# SUSTAINA-StrainGauge-Sensing-Board.net
KiCad netlist of a schematic drawn in EAGLE
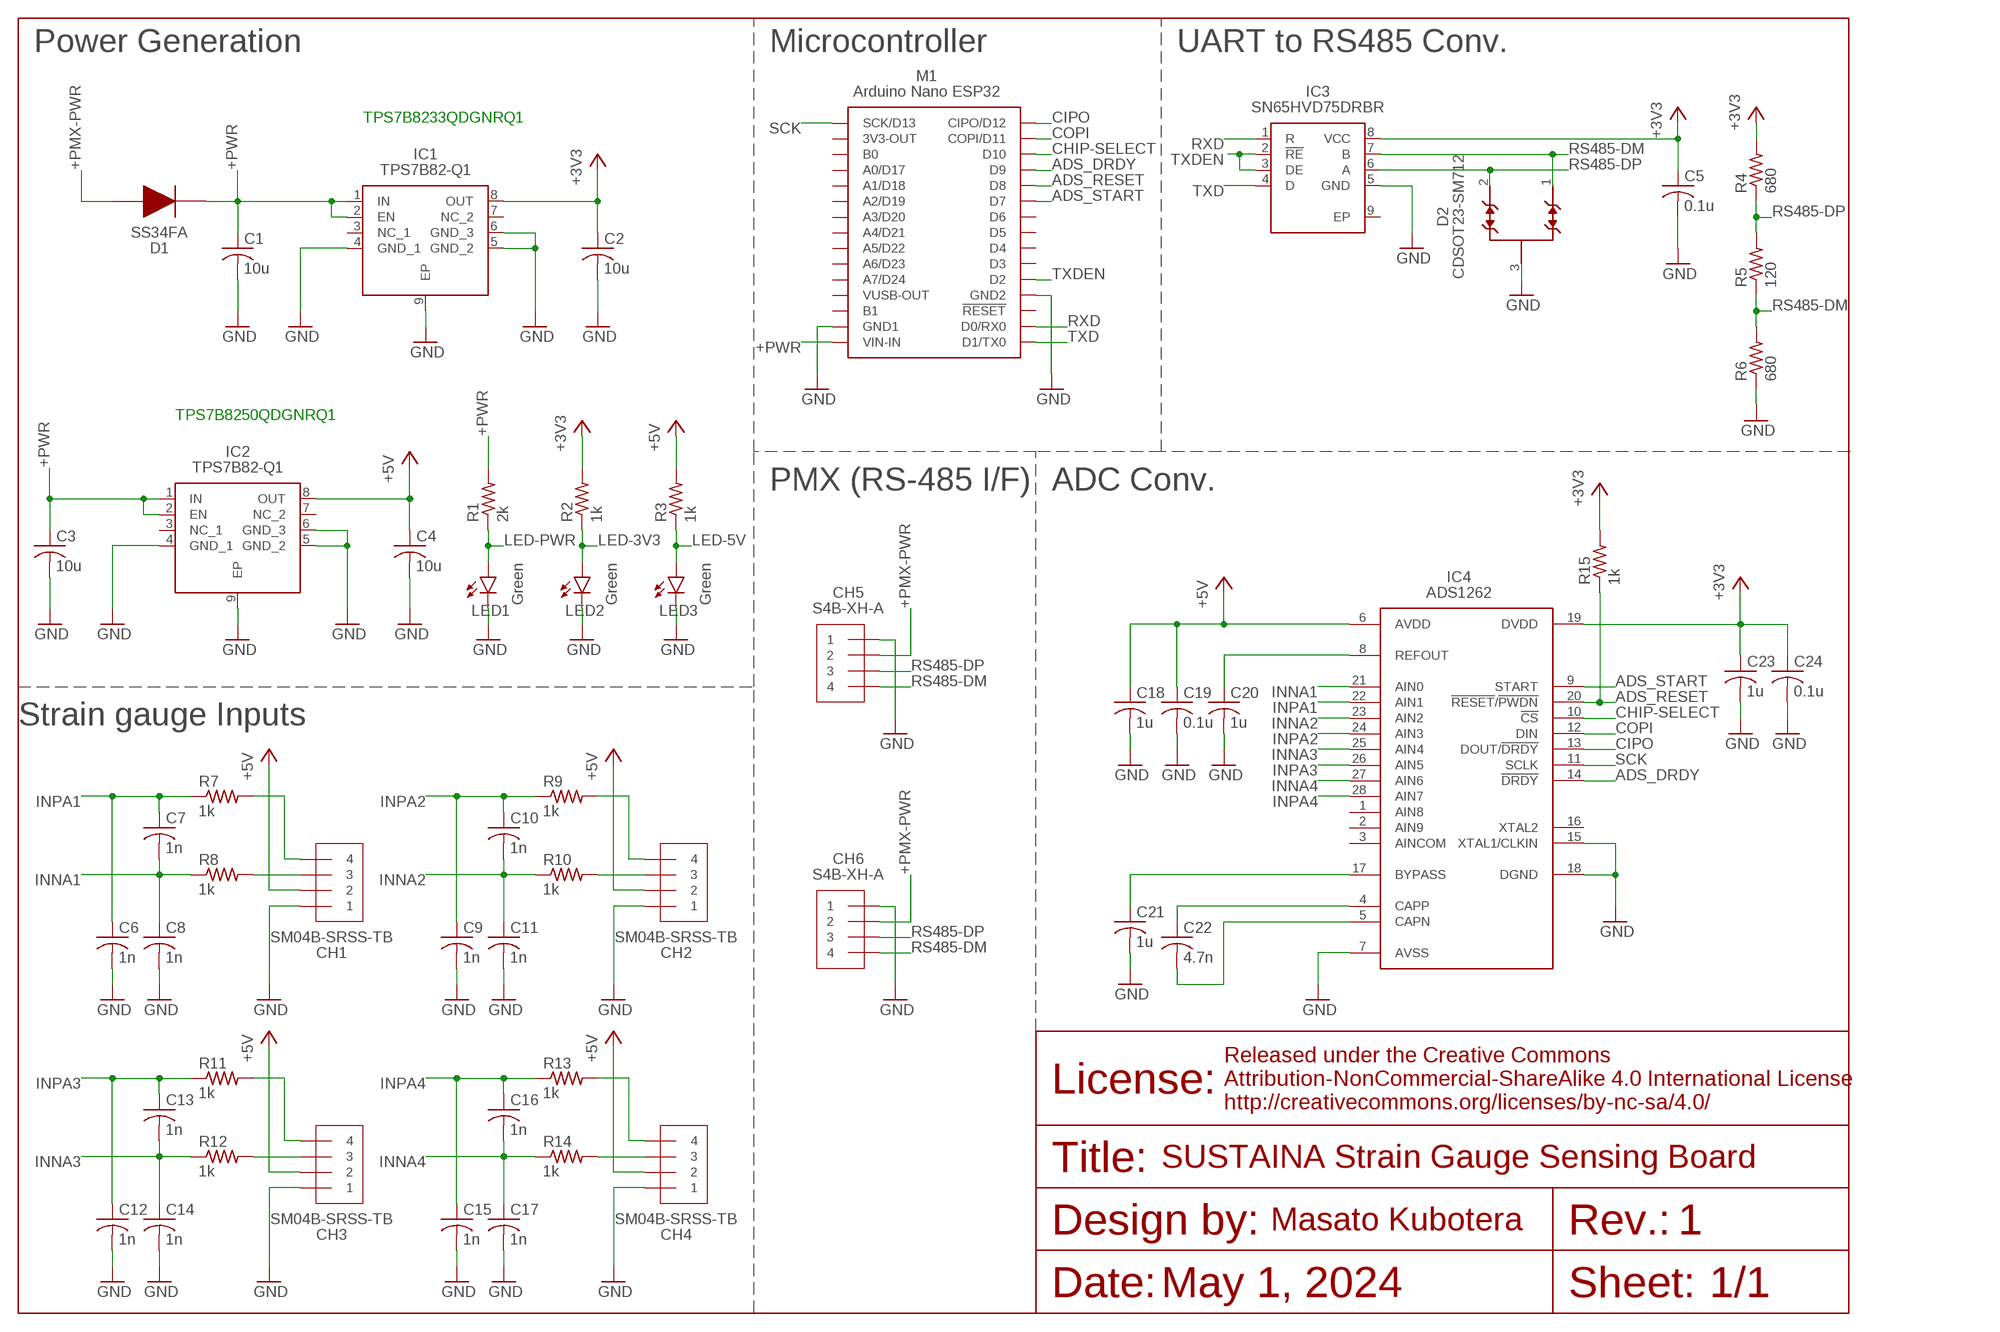
[diagram p0: schematic, sheet 1]

(export (version "E")
  (design (tool "Eeschema 10.0.6"))
  (components
    (comp (ref "C1")
      (value "10u")
      (footprint "eagle-import:C0603")
      (libsource (lib "eagle-import") (part "C-USC0603"))
    )
    (comp (ref "C2")
      (value "10u")
      (footprint "eagle-import:C0603")
      (libsource (lib "eagle-import") (part "C-USC0603"))
    )
    (comp (ref "C3")
      (value "10u")
      (footprint "eagle-import:C0603")
      (libsource (lib "eagle-import") (part "C-USC0603"))
    )
    (comp (ref "C4")
      (value "10u")
      (footprint "eagle-import:C0603")
      (libsource (lib "eagle-import") (part "C-USC0603"))
    )
    (comp (ref "C5")
      (value "0.1u")
      (footprint "eagle-import:C0603")
      (libsource (lib "eagle-import") (part "C-USC0603"))
    )
    (comp (ref "C6")
      (value "1n")
      (footprint "eagle-import:C0603")
      (libsource (lib "eagle-import") (part "C-USC0603"))
    )
    (comp (ref "C7")
      (value "1n")
      (footprint "eagle-import:C0603")
      (libsource (lib "eagle-import") (part "C-USC0603"))
    )
    (comp (ref "C8")
      (value "1n")
      (footprint "eagle-import:C0603")
      (libsource (lib "eagle-import") (part "C-USC0603"))
    )
    (comp (ref "C9")
      (value "1n")
      (footprint "eagle-import:C0603")
      (libsource (lib "eagle-import") (part "C-USC0603"))
    )
    (comp (ref "C10")
      (value "1n")
      (footprint "eagle-import:C0603")
      (libsource (lib "eagle-import") (part "C-USC0603"))
    )
    (comp (ref "C11")
      (value "1n")
      (footprint "eagle-import:C0603")
      (libsource (lib "eagle-import") (part "C-USC0603"))
    )
    (comp (ref "C12")
      (value "1n")
      (footprint "eagle-import:C0603")
      (libsource (lib "eagle-import") (part "C-USC0603"))
    )
    (comp (ref "C13")
      (value "1n")
      (footprint "eagle-import:C0603")
      (libsource (lib "eagle-import") (part "C-USC0603"))
    )
    (comp (ref "C14")
      (value "1n")
      (footprint "eagle-import:C0603")
      (libsource (lib "eagle-import") (part "C-USC0603"))
    )
    (comp (ref "C15")
      (value "1n")
      (footprint "eagle-import:C0603")
      (libsource (lib "eagle-import") (part "C-USC0603"))
    )
    (comp (ref "C16")
      (value "1n")
      (footprint "eagle-import:C0603")
      (libsource (lib "eagle-import") (part "C-USC0603"))
    )
    (comp (ref "C17")
      (value "1n")
      (footprint "eagle-import:C0603")
      (libsource (lib "eagle-import") (part "C-USC0603"))
    )
    (comp (ref "C18")
      (value "1u")
      (footprint "eagle-import:C0603")
      (libsource (lib "eagle-import") (part "C-USC0603"))
    )
    (comp (ref "C19")
      (value "0.1u")
      (footprint "eagle-import:C0603")
      (libsource (lib "eagle-import") (part "C-USC0603"))
    )
    (comp (ref "C20")
      (value "1u")
      (footprint "eagle-import:C0603")
      (libsource (lib "eagle-import") (part "C-USC0603"))
    )
    (comp (ref "C21")
      (value "1u")
      (footprint "eagle-import:C0603")
      (libsource (lib "eagle-import") (part "C-USC0603"))
    )
    (comp (ref "C22")
      (value "4.7n")
      (footprint "eagle-import:C0603")
      (libsource (lib "eagle-import") (part "C-USC0603"))
    )
    (comp (ref "C23")
      (value "1u")
      (footprint "eagle-import:C0603")
      (libsource (lib "eagle-import") (part "C-USC0603"))
    )
    (comp (ref "C24")
      (value "0.1u")
      (footprint "eagle-import:C0603")
      (libsource (lib "eagle-import") (part "C-USC0603"))
    )
    (comp (ref "CH1")
      (value "SM04B-SRSS-TB")
      (footprint "eagle-import:SM04B-SRSS-TB")
      (libsource (lib "eagle-import") (part "SM04B-SRSS-TB"))
    )
    (comp (ref "CH2")
      (value "SM04B-SRSS-TB")
      (footprint "eagle-import:SM04B-SRSS-TB")
      (libsource (lib "eagle-import") (part "SM04B-SRSS-TB"))
    )
    (comp (ref "CH3")
      (value "SM04B-SRSS-TB")
      (footprint "eagle-import:SM04B-SRSS-TB")
      (libsource (lib "eagle-import") (part "SM04B-SRSS-TB"))
    )
    (comp (ref "CH4")
      (value "SM04B-SRSS-TB")
      (footprint "eagle-import:SM04B-SRSS-TB")
      (libsource (lib "eagle-import") (part "SM04B-SRSS-TB"))
    )
    (comp (ref "CH5")
      (value "S4B-XH-A")
      (footprint "eagle-import:S4B-XH-A")
      (libsource (lib "eagle-import") (part "S4B-XH-A"))
    )
    (comp (ref "CH6")
      (value "S4B-XH-A")
      (footprint "eagle-import:S4B-XH-A")
      (libsource (lib "eagle-import") (part "S4B-XH-A"))
    )
    (comp (ref "D1")
      (value "SS34FA")
      (footprint "eagle-import:SS34FA")
      (libsource (lib "eagle-import") (part "SS34FA"))
    )
    (comp (ref "D2")
      (value "CDSOT23-SM712")
      (footprint "eagle-import:SOT-23-3")
      (libsource (lib "eagle-import") (part "CDSOT23-SM712"))
    )
    (comp (ref "IC1")
      (value "TPS7B82-Q1")
      (footprint "eagle-import:SOP65P490X110-9N")
      (libsource (lib "eagle-import") (part "TPS7B82-Q1"))
    )
    (comp (ref "IC2")
      (value "TPS7B82-Q1")
      (footprint "eagle-import:SOP65P490X110-9N")
      (libsource (lib "eagle-import") (part "TPS7B82-Q1"))
    )
    (comp (ref "IC3")
      (value "SN65HVD75DRBR")
      (footprint "eagle-import:SON65P300X300X100-9N")
      (libsource (lib "eagle-import") (part "SN65HVD75DRBR"))
    )
    (comp (ref "IC4")
      (value "ADS1262")
      (footprint "eagle-import:SOP65P640X120-28N")
      (libsource (lib "eagle-import") (part "ADS1262"))
    )
    (comp (ref "LED1")
      (value "Green")
      (footprint "eagle-import:SML0603")
      (libsource (lib "eagle-import") (part "LEDSML0603"))
    )
    (comp (ref "LED2")
      (value "Green")
      (footprint "eagle-import:SML0603")
      (libsource (lib "eagle-import") (part "LEDSML0603"))
    )
    (comp (ref "LED3")
      (value "Green")
      (footprint "eagle-import:SML0603")
      (libsource (lib "eagle-import") (part "LEDSML0603"))
    )
    (comp (ref "M1")
      (value "NANO-ESP32SMD")
      (footprint "eagle-import:NANO-ESP32-SMD")
      (libsource (lib "eagle-import") (part "NANO-ESP32SMD"))
    )
    (comp (ref "R1")
      (value "2k")
      (footprint "eagle-import:R0603")
      (libsource (lib "eagle-import") (part "R-US_R0603"))
    )
    (comp (ref "R2")
      (value "1k")
      (footprint "eagle-import:R0603")
      (libsource (lib "eagle-import") (part "R-US_R0603"))
    )
    (comp (ref "R3")
      (value "1k")
      (footprint "eagle-import:R0603")
      (libsource (lib "eagle-import") (part "R-US_R0603"))
    )
    (comp (ref "R4")
      (value "680")
      (footprint "eagle-import:R0603")
      (libsource (lib "eagle-import") (part "R-US_R0603"))
    )
    (comp (ref "R5")
      (value "120")
      (footprint "eagle-import:R0603")
      (libsource (lib "eagle-import") (part "R-US_R0603"))
    )
    (comp (ref "R6")
      (value "680")
      (footprint "eagle-import:R0603")
      (libsource (lib "eagle-import") (part "R-US_R0603"))
    )
    (comp (ref "R7")
      (value "1k")
      (footprint "eagle-import:R0603")
      (libsource (lib "eagle-import") (part "R-US_R0603"))
    )
    (comp (ref "R8")
      (value "1k")
      (footprint "eagle-import:R0603")
      (libsource (lib "eagle-import") (part "R-US_R0603"))
    )
    (comp (ref "R9")
      (value "1k")
      (footprint "eagle-import:R0603")
      (libsource (lib "eagle-import") (part "R-US_R0603"))
    )
    (comp (ref "R10")
      (value "1k")
      (footprint "eagle-import:R0603")
      (libsource (lib "eagle-import") (part "R-US_R0603"))
    )
    (comp (ref "R11")
      (value "1k")
      (footprint "eagle-import:R0603")
      (libsource (lib "eagle-import") (part "R-US_R0603"))
    )
    (comp (ref "R12")
      (value "1k")
      (footprint "eagle-import:R0603")
      (libsource (lib "eagle-import") (part "R-US_R0603"))
    )
    (comp (ref "R13")
      (value "1k")
      (footprint "eagle-import:R0603")
      (libsource (lib "eagle-import") (part "R-US_R0603"))
    )
    (comp (ref "R14")
      (value "1k")
      (footprint "eagle-import:R0603")
      (libsource (lib "eagle-import") (part "R-US_R0603"))
    )
    (comp (ref "R15")
      (value "1k")
      (footprint "eagle-import:R0603")
      (libsource (lib "eagle-import") (part "R-US_R0603"))
    )
  )
  (nets
    (net (code "1") (name "+3V3") (class "Default")
      (node (ref "C2") (pin "1") (pinfunction "1_1") (pintype "passive"))
      (node (ref "C23") (pin "1") (pinfunction "1_1") (pintype "passive"))
      (node (ref "C24") (pin "1") (pinfunction "1_1") (pintype "passive"))
      (node (ref "C5") (pin "1") (pinfunction "1_1") (pintype "passive"))
      (node (ref "IC1") (pin "8") (pinfunction "OUT_8") (pintype "bidirectional"))
      (node (ref "IC3") (pin "8") (pinfunction "VCC_8") (pintype "bidirectional"))
      (node (ref "IC4") (pin "19") (pinfunction "DVDD_19") (pintype "bidirectional"))
      (node (ref "R15") (pin "2") (pinfunction "2_2") (pintype "passive"))
      (node (ref "R2") (pin "2") (pinfunction "2_2") (pintype "passive"))
      (node (ref "R4") (pin "2") (pinfunction "2_2") (pintype "passive"))
    )
    (net (code "2") (name "+5V") (class "Default")
      (node (ref "C18") (pin "1") (pinfunction "1_1") (pintype "passive"))
      (node (ref "C19") (pin "1") (pinfunction "1_1") (pintype "passive"))
      (node (ref "C4") (pin "1") (pinfunction "1_1") (pintype "passive"))
      (node (ref "CH1") (pin "2") (pinfunction "2_2") (pintype "bidirectional"))
      (node (ref "CH2") (pin "2") (pinfunction "2_2") (pintype "bidirectional"))
      (node (ref "CH3") (pin "2") (pinfunction "2_2") (pintype "bidirectional"))
      (node (ref "CH4") (pin "2") (pinfunction "2_2") (pintype "bidirectional"))
      (node (ref "IC2") (pin "8") (pinfunction "OUT_8") (pintype "bidirectional"))
      (node (ref "IC4") (pin "6") (pinfunction "AVDD_6") (pintype "bidirectional"))
      (node (ref "R3") (pin "2") (pinfunction "2_2") (pintype "passive"))
    )
    (net (code "3") (name "/+PMX-PWR") (class "Default")
      (node (ref "CH5") (pin "2") (pinfunction "2_2") (pintype "bidirectional"))
      (node (ref "CH6") (pin "2") (pinfunction "2_2") (pintype "bidirectional"))
      (node (ref "D1") (pin "2") (pinfunction "2_2") (pintype "bidirectional"))
    )
    (net (code "4") (name "/+PWR") (class "Default")
      (node (ref "C1") (pin "1") (pinfunction "1_1") (pintype "passive"))
      (node (ref "C3") (pin "1") (pinfunction "1_1") (pintype "passive"))
      (node (ref "D1") (pin "1") (pinfunction "1_1") (pintype "bidirectional"))
      (node (ref "IC1") (pin "1") (pinfunction "IN_1") (pintype "bidirectional"))
      (node (ref "IC1") (pin "2") (pinfunction "EN_2") (pintype "bidirectional"))
      (node (ref "IC2") (pin "1") (pinfunction "IN_1") (pintype "bidirectional"))
      (node (ref "IC2") (pin "2") (pinfunction "EN_2") (pintype "bidirectional"))
      (node (ref "M1") (pin "VIN-IN") (pinfunction "VIN-IN_VIN-IN") (pintype "bidirectional"))
      (node (ref "R1") (pin "2") (pinfunction "2_2") (pintype "passive"))
    )
    (net (code "5") (name "/ADS_DRDY") (class "Default")
      (node (ref "IC4") (pin "14") (pinfunction "~{DRDY}_14") (pintype "bidirectional"))
      (node (ref "M1") (pin "D9") (pinfunction "D9_D9") (pintype "bidirectional"))
    )
    (net (code "6") (name "/ADS_RESET") (class "Default")
      (node (ref "IC4") (pin "20") (pinfunction "~{RESET}/~{PWDN}_20") (pintype "bidirectional"))
      (node (ref "M1") (pin "D8") (pinfunction "D8_D8") (pintype "bidirectional"))
      (node (ref "R15") (pin "1") (pinfunction "1_1") (pintype "passive"))
    )
    (net (code "7") (name "/ADS_START") (class "Default")
      (node (ref "IC4") (pin "9") (pinfunction "START_9") (pintype "bidirectional"))
      (node (ref "M1") (pin "D7") (pinfunction "D7_D7") (pintype "bidirectional"))
    )
    (net (code "8") (name "/CHIP-SELECT") (class "Default")
      (node (ref "IC4") (pin "10") (pinfunction "~{CS}_10") (pintype "bidirectional"))
      (node (ref "M1") (pin "D10") (pinfunction "D10_D10") (pintype "bidirectional"))
    )
    (net (code "9") (name "/CIPO") (class "Default")
      (node (ref "IC4") (pin "13") (pinfunction "DOUT/~{DRDY}_13") (pintype "bidirectional"))
      (node (ref "M1") (pin "CIPO/D12") (pinfunction "CIPO/D12_CIPO/D12") (pintype "bidirectional"))
    )
    (net (code "10") (name "/COPI") (class "Default")
      (node (ref "IC4") (pin "12") (pinfunction "DIN_12") (pintype "bidirectional"))
      (node (ref "M1") (pin "COPI/D11") (pinfunction "COPI/D11_COPI/D11") (pintype "bidirectional"))
    )
    (net (code "11") (name "/INNA1") (class "Default")
      (node (ref "C7") (pin "2") (pinfunction "2_2") (pintype "passive"))
      (node (ref "C8") (pin "1") (pinfunction "1_1") (pintype "passive"))
      (node (ref "IC4") (pin "21") (pinfunction "AIN0_21") (pintype "bidirectional"))
      (node (ref "R8") (pin "1") (pinfunction "1_1") (pintype "passive"))
    )
    (net (code "12") (name "/INNA2") (class "Default")
      (node (ref "C10") (pin "2") (pinfunction "2_2") (pintype "passive"))
      (node (ref "C11") (pin "1") (pinfunction "1_1") (pintype "passive"))
      (node (ref "IC4") (pin "23") (pinfunction "AIN2_23") (pintype "bidirectional"))
      (node (ref "R10") (pin "1") (pinfunction "1_1") (pintype "passive"))
    )
    (net (code "13") (name "/INNA3") (class "Default")
      (node (ref "C13") (pin "2") (pinfunction "2_2") (pintype "passive"))
      (node (ref "C14") (pin "1") (pinfunction "1_1") (pintype "passive"))
      (node (ref "IC4") (pin "25") (pinfunction "AIN4_25") (pintype "bidirectional"))
      (node (ref "R12") (pin "1") (pinfunction "1_1") (pintype "passive"))
    )
    (net (code "14") (name "/INNA4") (class "Default")
      (node (ref "C16") (pin "2") (pinfunction "2_2") (pintype "passive"))
      (node (ref "C17") (pin "1") (pinfunction "1_1") (pintype "passive"))
      (node (ref "IC4") (pin "27") (pinfunction "AIN6_27") (pintype "bidirectional"))
      (node (ref "R14") (pin "1") (pinfunction "1_1") (pintype "passive"))
    )
    (net (code "15") (name "/INPA1") (class "Default")
      (node (ref "C6") (pin "1") (pinfunction "1_1") (pintype "passive"))
      (node (ref "C7") (pin "1") (pinfunction "1_1") (pintype "passive"))
      (node (ref "IC4") (pin "22") (pinfunction "AIN1_22") (pintype "bidirectional"))
      (node (ref "R7") (pin "1") (pinfunction "1_1") (pintype "passive"))
    )
    (net (code "16") (name "/INPA2") (class "Default")
      (node (ref "C10") (pin "1") (pinfunction "1_1") (pintype "passive"))
      (node (ref "C9") (pin "1") (pinfunction "1_1") (pintype "passive"))
      (node (ref "IC4") (pin "24") (pinfunction "AIN3_24") (pintype "bidirectional"))
      (node (ref "R9") (pin "1") (pinfunction "1_1") (pintype "passive"))
    )
    (net (code "17") (name "/INPA3") (class "Default")
      (node (ref "C12") (pin "1") (pinfunction "1_1") (pintype "passive"))
      (node (ref "C13") (pin "1") (pinfunction "1_1") (pintype "passive"))
      (node (ref "IC4") (pin "26") (pinfunction "AIN5_26") (pintype "bidirectional"))
      (node (ref "R11") (pin "1") (pinfunction "1_1") (pintype "passive"))
    )
    (net (code "18") (name "/INPA4") (class "Default")
      (node (ref "C15") (pin "1") (pinfunction "1_1") (pintype "passive"))
      (node (ref "C16") (pin "1") (pinfunction "1_1") (pintype "passive"))
      (node (ref "IC4") (pin "28") (pinfunction "AIN7_28") (pintype "bidirectional"))
      (node (ref "R13") (pin "1") (pinfunction "1_1") (pintype "passive"))
    )
    (net (code "19") (name "/LED-3V3") (class "Default")
      (node (ref "LED2") (pin "A") (pinfunction "A_A") (pintype "passive"))
      (node (ref "R2") (pin "1") (pinfunction "1_1") (pintype "passive"))
    )
    (net (code "20") (name "/LED-5V") (class "Default")
      (node (ref "LED3") (pin "A") (pinfunction "A_A") (pintype "passive"))
      (node (ref "R3") (pin "1") (pinfunction "1_1") (pintype "passive"))
    )
    (net (code "21") (name "/LED-PWR") (class "Default")
      (node (ref "LED1") (pin "A") (pinfunction "A_A") (pintype "passive"))
      (node (ref "R1") (pin "1") (pinfunction "1_1") (pintype "passive"))
    )
    (net (code "22") (name "/RS485-DM") (class "Default")
      (node (ref "CH5") (pin "4") (pinfunction "4_4") (pintype "bidirectional"))
      (node (ref "CH6") (pin "4") (pinfunction "4_4") (pintype "bidirectional"))
      (node (ref "D2") (pin "1") (pinfunction "1_1") (pintype "bidirectional"))
      (node (ref "IC3") (pin "7") (pinfunction "B_7") (pintype "bidirectional"))
      (node (ref "R5") (pin "1") (pinfunction "1_1") (pintype "passive"))
      (node (ref "R6") (pin "2") (pinfunction "2_2") (pintype "passive"))
    )
    (net (code "23") (name "/RS485-DP") (class "Default")
      (node (ref "CH5") (pin "3") (pinfunction "3_3") (pintype "bidirectional"))
      (node (ref "CH6") (pin "3") (pinfunction "3_3") (pintype "bidirectional"))
      (node (ref "D2") (pin "2") (pinfunction "2_2") (pintype "bidirectional"))
      (node (ref "IC3") (pin "6") (pinfunction "A_6") (pintype "bidirectional"))
      (node (ref "R4") (pin "1") (pinfunction "1_1") (pintype "passive"))
      (node (ref "R5") (pin "2") (pinfunction "2_2") (pintype "passive"))
    )
    (net (code "24") (name "/RXD") (class "Default")
      (node (ref "IC3") (pin "1") (pinfunction "R_1") (pintype "bidirectional"))
      (node (ref "M1") (pin "D0/RX0") (pinfunction "D0/RX0_D0/RX0") (pintype "bidirectional"))
    )
    (net (code "25") (name "/SCK") (class "Default")
      (node (ref "IC4") (pin "11") (pinfunction "SCLK_11") (pintype "bidirectional"))
      (node (ref "M1") (pin "SCK/D13") (pinfunction "SCK/D13_SCK/D13") (pintype "bidirectional"))
    )
    (net (code "26") (name "/TXD") (class "Default")
      (node (ref "IC3") (pin "4") (pinfunction "D_4") (pintype "bidirectional"))
      (node (ref "M1") (pin "D1/TX0") (pinfunction "D1/TX0_D1/TX0") (pintype "bidirectional"))
    )
    (net (code "27") (name "/TXDEN") (class "Default")
      (node (ref "IC3") (pin "2") (pinfunction "~{RE}_2") (pintype "bidirectional"))
      (node (ref "IC3") (pin "3") (pinfunction "DE_3") (pintype "bidirectional"))
      (node (ref "M1") (pin "D2") (pinfunction "D2_D2") (pintype "bidirectional"))
    )
    (net (code "28") (name "GND") (class "Default")
      (node (ref "C1") (pin "2") (pinfunction "2_2") (pintype "passive"))
      (node (ref "C11") (pin "2") (pinfunction "2_2") (pintype "passive"))
      (node (ref "C12") (pin "2") (pinfunction "2_2") (pintype "passive"))
      (node (ref "C14") (pin "2") (pinfunction "2_2") (pintype "passive"))
      (node (ref "C15") (pin "2") (pinfunction "2_2") (pintype "passive"))
      (node (ref "C17") (pin "2") (pinfunction "2_2") (pintype "passive"))
      (node (ref "C18") (pin "2") (pinfunction "2_2") (pintype "passive"))
      (node (ref "C19") (pin "2") (pinfunction "2_2") (pintype "passive"))
      (node (ref "C2") (pin "2") (pinfunction "2_2") (pintype "passive"))
      (node (ref "C20") (pin "2") (pinfunction "2_2") (pintype "passive"))
      (node (ref "C21") (pin "2") (pinfunction "2_2") (pintype "passive"))
      (node (ref "C23") (pin "2") (pinfunction "2_2") (pintype "passive"))
      (node (ref "C24") (pin "2") (pinfunction "2_2") (pintype "passive"))
      (node (ref "C3") (pin "2") (pinfunction "2_2") (pintype "passive"))
      (node (ref "C4") (pin "2") (pinfunction "2_2") (pintype "passive"))
      (node (ref "C5") (pin "2") (pinfunction "2_2") (pintype "passive"))
      (node (ref "C6") (pin "2") (pinfunction "2_2") (pintype "passive"))
      (node (ref "C8") (pin "2") (pinfunction "2_2") (pintype "passive"))
      (node (ref "C9") (pin "2") (pinfunction "2_2") (pintype "passive"))
      (node (ref "CH1") (pin "1") (pinfunction "1_1") (pintype "bidirectional"))
      (node (ref "CH2") (pin "1") (pinfunction "1_1") (pintype "bidirectional"))
      (node (ref "CH3") (pin "1") (pinfunction "1_1") (pintype "bidirectional"))
      (node (ref "CH4") (pin "1") (pinfunction "1_1") (pintype "bidirectional"))
      (node (ref "CH5") (pin "1") (pinfunction "1_1") (pintype "bidirectional"))
      (node (ref "CH6") (pin "1") (pinfunction "1_1") (pintype "bidirectional"))
      (node (ref "D2") (pin "3") (pinfunction "3_3") (pintype "bidirectional"))
      (node (ref "IC1") (pin "4") (pinfunction "GND_1_4") (pintype "bidirectional"))
      (node (ref "IC1") (pin "5") (pinfunction "GND_2_5") (pintype "bidirectional"))
      (node (ref "IC1") (pin "6") (pinfunction "GND_3_6") (pintype "bidirectional"))
      (node (ref "IC1") (pin "9") (pinfunction "EP_9") (pintype "bidirectional"))
      (node (ref "IC2") (pin "4") (pinfunction "GND_1_4") (pintype "bidirectional"))
      (node (ref "IC2") (pin "5") (pinfunction "GND_2_5") (pintype "bidirectional"))
      (node (ref "IC2") (pin "6") (pinfunction "GND_3_6") (pintype "bidirectional"))
      (node (ref "IC2") (pin "9") (pinfunction "EP_9") (pintype "bidirectional"))
      (node (ref "IC3") (pin "5") (pinfunction "GND_5") (pintype "bidirectional"))
      (node (ref "IC4") (pin "15") (pinfunction "XTAL1/CLKIN_15") (pintype "bidirectional"))
      (node (ref "IC4") (pin "18") (pinfunction "DGND_18") (pintype "bidirectional"))
      (node (ref "IC4") (pin "7") (pinfunction "AVSS_7") (pintype "bidirectional"))
      (node (ref "LED1") (pin "C") (pinfunction "C_C") (pintype "passive"))
      (node (ref "LED2") (pin "C") (pinfunction "C_C") (pintype "passive"))
      (node (ref "LED3") (pin "C") (pinfunction "C_C") (pintype "passive"))
      (node (ref "M1") (pin "GND1") (pinfunction "GND1_GND1") (pintype "bidirectional"))
      (node (ref "M1") (pin "GND2") (pinfunction "GND2_GND2") (pintype "bidirectional"))
      (node (ref "R6") (pin "1") (pinfunction "1_1") (pintype "passive"))
    )
    (net (code "29") (name "Net-(CH1-Pad3)") (class "Default")
      (node (ref "CH1") (pin "3") (pinfunction "3_3") (pintype "bidirectional"))
      (node (ref "R8") (pin "2") (pinfunction "2_2") (pintype "passive"))
    )
    (net (code "30") (name "Net-(CH1-Pad4)") (class "Default")
      (node (ref "CH1") (pin "4") (pinfunction "4_4") (pintype "bidirectional"))
      (node (ref "R7") (pin "2") (pinfunction "2_2") (pintype "passive"))
    )
    (net (code "31") (name "Net-(CH2-Pad3)") (class "Default")
      (node (ref "CH2") (pin "3") (pinfunction "3_3") (pintype "bidirectional"))
      (node (ref "R10") (pin "2") (pinfunction "2_2") (pintype "passive"))
    )
    (net (code "32") (name "Net-(CH2-Pad4)") (class "Default")
      (node (ref "CH2") (pin "4") (pinfunction "4_4") (pintype "bidirectional"))
      (node (ref "R9") (pin "2") (pinfunction "2_2") (pintype "passive"))
    )
    (net (code "33") (name "Net-(CH3-Pad3)") (class "Default")
      (node (ref "CH3") (pin "3") (pinfunction "3_3") (pintype "bidirectional"))
      (node (ref "R12") (pin "2") (pinfunction "2_2") (pintype "passive"))
    )
    (net (code "34") (name "Net-(CH3-Pad4)") (class "Default")
      (node (ref "CH3") (pin "4") (pinfunction "4_4") (pintype "bidirectional"))
      (node (ref "R11") (pin "2") (pinfunction "2_2") (pintype "passive"))
    )
    (net (code "35") (name "Net-(CH4-Pad3)") (class "Default")
      (node (ref "CH4") (pin "3") (pinfunction "3_3") (pintype "bidirectional"))
      (node (ref "R14") (pin "2") (pinfunction "2_2") (pintype "passive"))
    )
    (net (code "36") (name "Net-(CH4-Pad4)") (class "Default")
      (node (ref "CH4") (pin "4") (pinfunction "4_4") (pintype "bidirectional"))
      (node (ref "R13") (pin "2") (pinfunction "2_2") (pintype "passive"))
    )
    (net (code "37") (name "Net-(IC4-BYPASS)") (class "Default")
      (node (ref "C21") (pin "1") (pinfunction "1_1") (pintype "passive"))
      (node (ref "IC4") (pin "17") (pinfunction "BYPASS_17") (pintype "bidirectional"))
    )
    (net (code "38") (name "Net-(IC4-CAPN)") (class "Default")
      (node (ref "C22") (pin "2") (pinfunction "2_2") (pintype "passive"))
      (node (ref "IC4") (pin "5") (pinfunction "CAPN_5") (pintype "bidirectional"))
    )
    (net (code "39") (name "Net-(IC4-CAPP)") (class "Default")
      (node (ref "C22") (pin "1") (pinfunction "1_1") (pintype "passive"))
      (node (ref "IC4") (pin "4") (pinfunction "CAPP_4") (pintype "bidirectional"))
    )
    (net (code "40") (name "Net-(IC4-REFOUT)") (class "Default")
      (node (ref "C20") (pin "1") (pinfunction "1_1") (pintype "passive"))
      (node (ref "IC4") (pin "8") (pinfunction "REFOUT_8") (pintype "bidirectional"))
    )
    (net (code "41") (name "unconnected-(IC1-NC_1-Pad3)") (class "Default")
      (node (ref "IC1") (pin "3") (pinfunction "NC_1_3") (pintype "no_connect"))
    )
    (net (code "42") (name "unconnected-(IC1-NC_2-Pad7)") (class "Default")
      (node (ref "IC1") (pin "7") (pinfunction "NC_2_7") (pintype "no_connect"))
    )
    (net (code "43") (name "unconnected-(IC2-NC_1-Pad3)") (class "Default")
      (node (ref "IC2") (pin "3") (pinfunction "NC_1_3") (pintype "no_connect"))
    )
    (net (code "44") (name "unconnected-(IC2-NC_2-Pad7)") (class "Default")
      (node (ref "IC2") (pin "7") (pinfunction "NC_2_7") (pintype "no_connect"))
    )
    (net (code "45") (name "unconnected-(IC3-EP-Pad9)") (class "Default")
      (node (ref "IC3") (pin "9") (pinfunction "EP_9") (pintype "bidirectional"))
    )
    (net (code "46") (name "unconnected-(IC4-AIN8-Pad1)") (class "Default")
      (node (ref "IC4") (pin "1") (pinfunction "AIN8_1") (pintype "bidirectional"))
    )
    (net (code "47") (name "unconnected-(IC4-AIN9-Pad2)") (class "Default")
      (node (ref "IC4") (pin "2") (pinfunction "AIN9_2") (pintype "bidirectional"))
    )
    (net (code "48") (name "unconnected-(IC4-AINCOM-Pad3)") (class "Default")
      (node (ref "IC4") (pin "3") (pinfunction "AINCOM_3") (pintype "bidirectional"))
    )
    (net (code "49") (name "unconnected-(IC4-XTAL2-Pad16)") (class "Default")
      (node (ref "IC4") (pin "16") (pinfunction "XTAL2_16") (pintype "bidirectional"))
    )
    (net (code "50") (name "unconnected-(M1-Pad3V3-OUT)") (class "Default")
      (node (ref "M1") (pin "3V3-OUT") (pinfunction "3V3-OUT_3V3-OUT") (pintype "bidirectional"))
    )
    (net (code "51") (name "unconnected-(M1-PadA0{slash}D17)") (class "Default")
      (node (ref "M1") (pin "A0/D17") (pinfunction "A0/D17_A0/D17") (pintype "bidirectional"))
    )
    (net (code "52") (name "unconnected-(M1-PadA1{slash}D18)") (class "Default")
      (node (ref "M1") (pin "A1/D18") (pinfunction "A1/D18_A1/D18") (pintype "bidirectional"))
    )
    (net (code "53") (name "unconnected-(M1-PadA2{slash}D19)") (class "Default")
      (node (ref "M1") (pin "A2/D19") (pinfunction "A2/D19_A2/D19") (pintype "bidirectional"))
    )
    (net (code "54") (name "unconnected-(M1-PadA3{slash}D20)") (class "Default")
      (node (ref "M1") (pin "A3/D20") (pinfunction "A3/D20_A3/D20") (pintype "bidirectional"))
    )
    (net (code "55") (name "unconnected-(M1-PadA4{slash}D21)") (class "Default")
      (node (ref "M1") (pin "A4/D21") (pinfunction "A4/D21_A4/D21") (pintype "bidirectional"))
    )
    (net (code "56") (name "unconnected-(M1-PadA5{slash}D22)") (class "Default")
      (node (ref "M1") (pin "A5/D22") (pinfunction "A5/D22_A5/D22") (pintype "bidirectional"))
    )
    (net (code "57") (name "unconnected-(M1-PadA6{slash}D23)") (class "Default")
      (node (ref "M1") (pin "A6/D23") (pinfunction "A6/D23_A6/D23") (pintype "bidirectional"))
    )
    (net (code "58") (name "unconnected-(M1-PadA7{slash}D24)") (class "Default")
      (node (ref "M1") (pin "A7/D24") (pinfunction "A7/D24_A7/D24") (pintype "bidirectional"))
    )
    (net (code "59") (name "unconnected-(M1-PadB0)") (class "Default")
      (node (ref "M1") (pin "B0") (pinfunction "B0_B0") (pintype "bidirectional"))
    )
    (net (code "60") (name "unconnected-(M1-PadB1)") (class "Default")
      (node (ref "M1") (pin "B1") (pinfunction "B1_B1") (pintype "bidirectional"))
    )
    (net (code "61") (name "unconnected-(M1-PadD3)") (class "Default")
      (node (ref "M1") (pin "D3") (pinfunction "D3_D3") (pintype "bidirectional"))
    )
    (net (code "62") (name "unconnected-(M1-PadD4)") (class "Default")
      (node (ref "M1") (pin "D4") (pinfunction "D4_D4") (pintype "bidirectional"))
    )
    (net (code "63") (name "unconnected-(M1-PadD5)") (class "Default")
      (node (ref "M1") (pin "D5") (pinfunction "D5_D5") (pintype "bidirectional"))
    )
    (net (code "64") (name "unconnected-(M1-PadD6)") (class "Default")
      (node (ref "M1") (pin "D6") (pinfunction "D6_D6") (pintype "bidirectional"))
    )
    (net (code "65") (name "unconnected-(M1-PadVUSB-OUT)") (class "Default")
      (node (ref "M1") (pin "VUSB-OUT") (pinfunction "VUSB-OUT_VUSB-OUT") (pintype "bidirectional"))
    )
    (net (code "66") (name "unconnected-(M1-~{RESET}-Pad!RESET)") (class "Default")
      (node (ref "M1") (pin "!RESET") (pinfunction "~{RESET}_!RESET") (pintype "bidirectional"))
    )
  )
)
